# SCH.net
KiCad netlist of a schematic drawn in Altium Designer
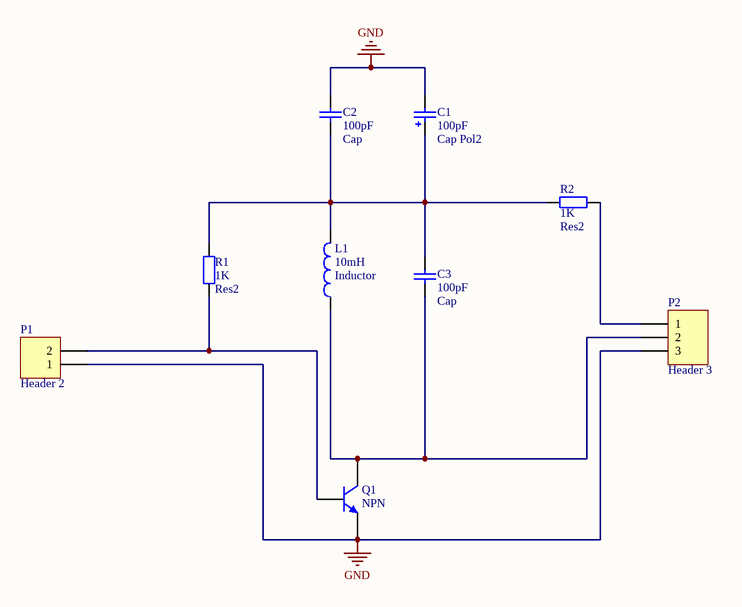
[diagram p0: SCH.SchDoc]

(export (version "E")
  (design (tool "Eeschema 10.0.6"))
  (components
    (comp (ref "C1")
      (value "Cap Pol2")
      (footprint "POLAR0.8")
      (description "Polarized Capacitor (Axial)")
      (fields (field (name "ALTIUM_VALUE") "100pF") (field (name "PUBLISHER") "Altium Limited"))
      (libsource (lib "Miscellaneous Devices") (part "Cap Pol2"))
    )
    (comp (ref "C2")
      (value "Cap")
      (footprint "RAD-0.3")
      (description "Capacitor")
      (fields (field (name "ALTIUM_VALUE") "100pF") (field (name "PUBLISHER") "Altium Limited"))
      (libsource (lib "Miscellaneous Devices") (part "Cap"))
    )
    (comp (ref "C3")
      (value "Cap")
      (footprint "RAD-0.3")
      (description "Capacitor")
      (fields (field (name "ALTIUM_VALUE") "100pF") (field (name "PUBLISHER") "Altium Limited"))
      (libsource (lib "Miscellaneous Devices") (part "Cap"))
    )
    (comp (ref "L1")
      (value "Inductor")
      (footprint "0402-A")
      (fields (field (name "ALTIUM_VALUE") "10mH") (field (name "PUBLISHER") "Altium Limited"))
      (libsource (lib "Miscellaneous Devices") (part "Inductor"))
    )
    (comp (ref "P1")
      (value "Header 2")
      (footprint "HDR1X2")
      (description "Header, 2-Pin")
      (fields (field (name "PUBLISHER") "Altium Limited"))
      (libsource (lib "Miscellaneous Connectors") (part "Header 2"))
    )
    (comp (ref "P2")
      (value "Header 3")
      (footprint "HDR1X3")
      (description "Header, 3-Pin")
      (fields (field (name "PUBLISHER") "Altium Limited"))
      (libsource (lib "Miscellaneous Connectors") (part "Header 3"))
    )
    (comp (ref "Q1")
      (value "NPN")
      (footprint "TO-226-AA")
      (description "NPN Bipolar Transistor")
      (fields (field (name "PUBLISHER") "Altium Limited"))
      (libsource (lib "Miscellaneous Devices") (part "NPN"))
    )
    (comp (ref "R1")
      (value "Res2")
      (footprint "AXIAL-0.4")
      (description "Resistor")
      (fields (field (name "ALTIUM_VALUE") "1K") (field (name "PUBLISHER") "Altium Limited"))
      (libsource (lib "Miscellaneous Devices") (part "Res2"))
    )
    (comp (ref "R2")
      (value "Res2")
      (footprint "AXIAL-0.4")
      (description "Resistor")
      (fields (field (name "ALTIUM_VALUE") "1K") (field (name "PUBLISHER") "Altium Limited"))
      (libsource (lib "") (part "Res2_1"))
    )
  )
  (nets
    (net (code "1") (name "GND") (class "Default")
      (node (ref "C1") (pin "2") (pinfunction "2_2") (pintype "passive"))
      (node (ref "C2") (pin "2") (pinfunction "2_2") (pintype "passive"))
      (node (ref "P1") (pin "1") (pinfunction "1_1") (pintype "passive"))
      (node (ref "P2") (pin "3") (pinfunction "3_3") (pintype "passive"))
      (node (ref "Q1") (pin "3") (pinfunction "E_3") (pintype "passive"))
    )
    (net (code "2") (name "Net-(C1-Pad1)") (class "Default")
      (node (ref "C1") (pin "1") (pinfunction "1_1") (pintype "passive"))
      (node (ref "C2") (pin "1") (pinfunction "1_1") (pintype "passive"))
      (node (ref "C3") (pin "2") (pinfunction "2_2") (pintype "passive"))
      (node (ref "L1") (pin "2") (pinfunction "2_2") (pintype "passive"))
      (node (ref "R1") (pin "2") (pinfunction "2_2") (pintype "passive"))
      (node (ref "R2") (pin "2") (pinfunction "2_2") (pintype "passive"))
    )
    (net (code "3") (name "Net-(P2-Pad1)") (class "Default")
      (node (ref "P2") (pin "1") (pinfunction "1_1") (pintype "passive"))
      (node (ref "R2") (pin "1") (pinfunction "1_1") (pintype "passive"))
    )
    (net (code "4") (name "Net-(Q1-B)") (class "Default")
      (node (ref "P1") (pin "2") (pinfunction "2_2") (pintype "passive"))
      (node (ref "Q1") (pin "2") (pinfunction "B_2") (pintype "passive"))
      (node (ref "R1") (pin "1") (pinfunction "1_1") (pintype "passive"))
    )
    (net (code "5") (name "Net-(Q1-C)") (class "Default")
      (node (ref "C3") (pin "1") (pinfunction "1_1") (pintype "passive"))
      (node (ref "L1") (pin "1") (pinfunction "1_1") (pintype "passive"))
      (node (ref "P2") (pin "2") (pinfunction "2_2") (pintype "passive"))
      (node (ref "Q1") (pin "1") (pinfunction "C_1") (pintype "passive"))
    )
  )
)
